# untitled.net
KiCad netlist of a schematic drawn in EAGLE
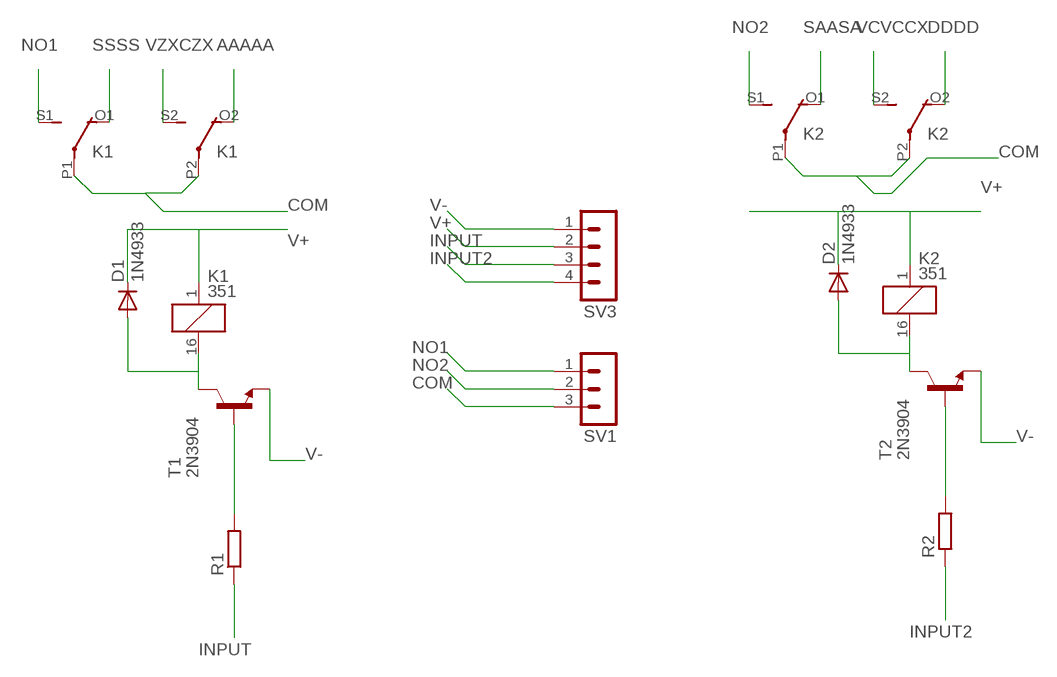
[diagram p0: schematic, sheet 1]

(export (version "E")
  (design (tool "Eeschema 10.0.6"))
  (components
    (comp (ref "D1")
      (value "1N4933")
      (footprint "eagle-import:DO41-10")
      (libsource (lib "eagle-import") (part "1N4933"))
    )
    (comp (ref "D2")
      (value "1N4933")
      (footprint "eagle-import:DO41-10")
      (libsource (lib "eagle-import") (part "1N4933"))
    )
    (comp (ref "K1")
      (value "351")
      (footprint "eagle-import:351")
      (libsource (lib "eagle-import") (part "351"))
    )
    (comp (ref "K2")
      (value "351")
      (footprint "eagle-import:351")
      (libsource (lib "eagle-import") (part "351"))
    )
    (comp (ref "R1")
      (value "R-EU_0309/12")
      (footprint "eagle-import:0309_12")
      (libsource (lib "eagle-import") (part "R-EU_0309/12"))
    )
    (comp (ref "R2")
      (value "R-EU_0309/12")
      (footprint "eagle-import:0309_12")
      (libsource (lib "eagle-import") (part "R-EU_0309/12"))
    )
    (comp (ref "SV1")
      (value "MA03-1")
      (footprint "eagle-import:MA03-1")
      (libsource (lib "eagle-import") (part "MA03-1"))
    )
    (comp (ref "SV3")
      (value "MA04-1")
      (footprint "eagle-import:MA04-1")
      (libsource (lib "eagle-import") (part "MA04-1"))
    )
    (comp (ref "T1")
      (value "2N3904")
      (footprint "eagle-import:TO92")
      (libsource (lib "eagle-import") (part "2N3904"))
    )
    (comp (ref "T2")
      (value "2N3904")
      (footprint "eagle-import:TO92")
      (libsource (lib "eagle-import") (part "2N3904"))
    )
  )
  (nets
    (net (code "1") (name "/AAAAA") (class "Default")
      (node (ref "K1") (pin "O2") (pinfunction "O_O2") (pintype "passive"))
    )
    (net (code "2") (name "/COM") (class "Default")
      (node (ref "K1") (pin "P1") (pinfunction "P_P1") (pintype "passive"))
      (node (ref "K1") (pin "P2") (pinfunction "P_P2") (pintype "passive"))
      (node (ref "K2") (pin "P1") (pinfunction "P_P1") (pintype "passive"))
      (node (ref "K2") (pin "P2") (pinfunction "P_P2") (pintype "passive"))
      (node (ref "SV1") (pin "3") (pinfunction "3_3") (pintype "passive"))
    )
    (net (code "3") (name "/DDDD") (class "Default")
      (node (ref "K2") (pin "O2") (pinfunction "O_O2") (pintype "passive"))
    )
    (net (code "4") (name "/INPUT") (class "Default")
      (node (ref "R1") (pin "1") (pinfunction "1_1") (pintype "passive"))
      (node (ref "SV3") (pin "3") (pinfunction "3_3") (pintype "passive"))
    )
    (net (code "5") (name "/INPUT2") (class "Default")
      (node (ref "R2") (pin "1") (pinfunction "1_1") (pintype "passive"))
      (node (ref "SV3") (pin "4") (pinfunction "4_4") (pintype "passive"))
    )
    (net (code "6") (name "/NO1") (class "Default")
      (node (ref "K1") (pin "S1") (pinfunction "S_S1") (pintype "passive"))
      (node (ref "SV1") (pin "1") (pinfunction "1_1") (pintype "passive"))
    )
    (net (code "7") (name "/NO2") (class "Default")
      (node (ref "K2") (pin "S1") (pinfunction "S_S1") (pintype "passive"))
      (node (ref "SV1") (pin "2") (pinfunction "2_2") (pintype "passive"))
    )
    (net (code "8") (name "/SAASA") (class "Default")
      (node (ref "K2") (pin "O1") (pinfunction "O_O1") (pintype "passive"))
    )
    (net (code "9") (name "/SSSS") (class "Default")
      (node (ref "K1") (pin "O1") (pinfunction "O_O1") (pintype "passive"))
    )
    (net (code "10") (name "/V+") (class "Default")
      (node (ref "D1") (pin "C") (pinfunction "C_C") (pintype "passive"))
      (node (ref "D2") (pin "C") (pinfunction "C_C") (pintype "passive"))
      (node (ref "K1") (pin "1") (pinfunction "1_1") (pintype "passive"))
      (node (ref "K2") (pin "1") (pinfunction "1_1") (pintype "passive"))
      (node (ref "SV3") (pin "2") (pinfunction "2_2") (pintype "passive"))
    )
    (net (code "11") (name "/V-") (class "Default")
      (node (ref "SV3") (pin "1") (pinfunction "1_1") (pintype "passive"))
      (node (ref "T1") (pin "3") (pinfunction "E_3") (pintype "passive"))
      (node (ref "T2") (pin "3") (pinfunction "E_3") (pintype "passive"))
    )
    (net (code "12") (name "/VCVCCX") (class "Default")
      (node (ref "K2") (pin "S2") (pinfunction "S_S2") (pintype "passive"))
    )
    (net (code "13") (name "/VZXCZX") (class "Default")
      (node (ref "K1") (pin "S2") (pinfunction "S_S2") (pintype "passive"))
    )
    (net (code "14") (name "Net-(K1A-2)") (class "Default")
      (node (ref "D1") (pin "A") (pinfunction "A_A") (pintype "passive"))
      (node (ref "K1") (pin "16") (pinfunction "2_16") (pintype "passive"))
      (node (ref "T1") (pin "1") (pinfunction "C_1") (pintype "passive"))
    )
    (net (code "15") (name "Net-(K2A-2)") (class "Default")
      (node (ref "D2") (pin "A") (pinfunction "A_A") (pintype "passive"))
      (node (ref "K2") (pin "16") (pinfunction "2_16") (pintype "passive"))
      (node (ref "T2") (pin "1") (pinfunction "C_1") (pintype "passive"))
    )
    (net (code "16") (name "Net-(T1-B)") (class "Default")
      (node (ref "R1") (pin "2") (pinfunction "2_2") (pintype "passive"))
      (node (ref "T1") (pin "2") (pinfunction "B_2") (pintype "passive"))
    )
    (net (code "17") (name "Net-(T2-B)") (class "Default")
      (node (ref "R2") (pin "2") (pinfunction "2_2") (pintype "passive"))
      (node (ref "T2") (pin "2") (pinfunction "B_2") (pintype "passive"))
    )
  )
)
